# USB_CAMERA.net
KiCad netlist of a schematic drawn in Altium Designer
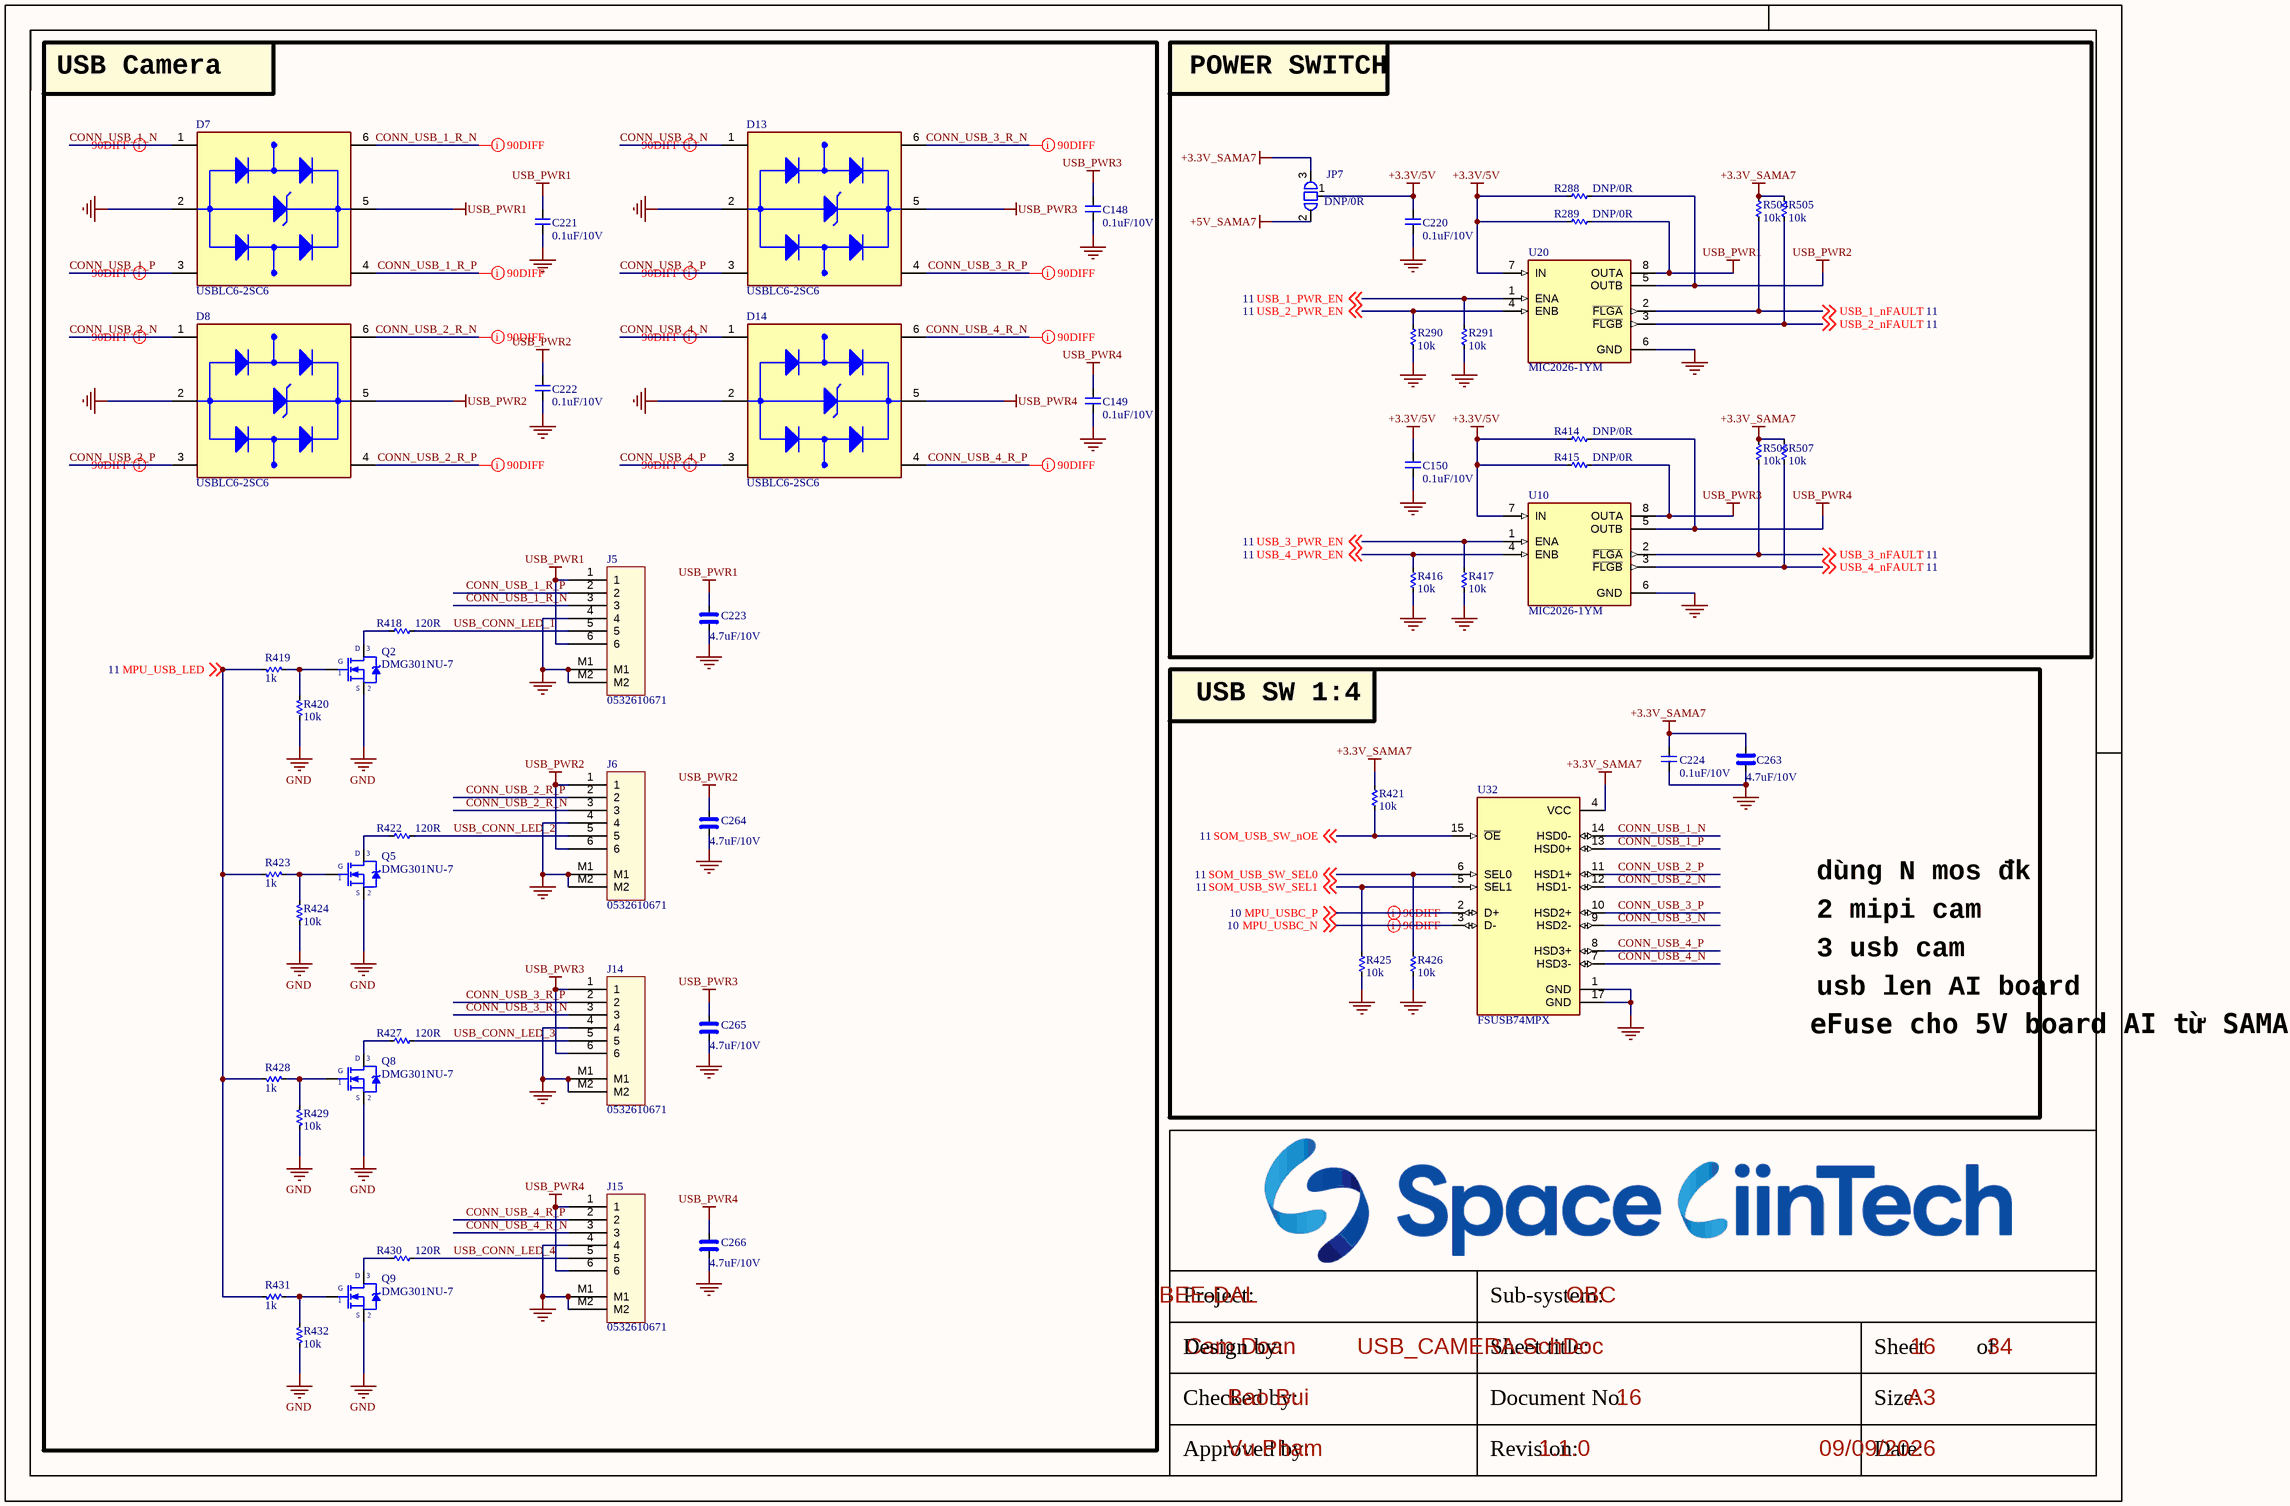
[diagram p0: USB_CAMERA.SchDoc]

(export (version "E")
  (design (tool "Eeschema 10.0.6"))
  (components
    (comp (ref "C148")
      (value "0.1uF/10V")
      (footprint "CAP_C_1005X50_L")
      (description "CAP")
      (libsource (lib "LABLIB") (part "_CAP_C_2"))
    )
    (comp (ref "C149")
      (value "0.1uF/10V")
      (footprint "CAP_C_1005X50_L")
      (description "CAP")
      (libsource (lib "LABLIB") (part "_CAP_C_2"))
    )
    (comp (ref "C150")
      (value "0.1uF/10V")
      (footprint "CAP_C_1005X50_L")
      (description "CAP")
      (libsource (lib "LABLIB") (part "_CAP_C_2"))
    )
    (comp (ref "C220")
      (value "0.1uF/10V")
      (footprint "CAP_C_1005X50_L")
      (description "CAP")
      (libsource (lib "LABLIB") (part "_CAP_C_2"))
    )
    (comp (ref "C221")
      (value "0.1uF/10V")
      (footprint "CAP_C_1005X50_L")
      (description "CAP")
      (libsource (lib "LABLIB") (part "_CAP_C_2"))
    )
    (comp (ref "C222")
      (value "0.1uF/10V")
      (footprint "CAP_C_1005X50_L")
      (description "CAP")
      (libsource (lib "LABLIB") (part "_CAP_C_2"))
    )
    (comp (ref "C223")
      (value "4.7uF/10V")
      (footprint "CAP_C_1005X60")
      (description "CAP CHIP High Value")
      (libsource (lib "LABLIB") (part "_CAP_C_High_2"))
    )
    (comp (ref "C224")
      (value "0.1uF/10V")
      (footprint "CAP_C_1005X50_L")
      (description "CAP CHIP")
      (libsource (lib "LABLIB") (part "_CAP_C_2"))
    )
    (comp (ref "C263")
      (value "4.7uF/10V")
      (footprint "CAP_C_1005X60")
      (description "CAP CHIP High Value")
      (libsource (lib "LABLIB") (part "_CAP_C_High_2"))
    )
    (comp (ref "C264")
      (value "4.7uF/10V")
      (footprint "CAP_C_1005X60")
      (description "CAP CHIP High Value")
      (libsource (lib "LABLIB") (part "_CAP_C_High_2"))
    )
    (comp (ref "C265")
      (value "4.7uF/10V")
      (footprint "CAP_C_1005X60")
      (description "CAP CHIP High Value")
      (libsource (lib "LABLIB") (part "_CAP_C_High_2"))
    )
    (comp (ref "C266")
      (value "4.7uF/10V")
      (footprint "CAP_C_1005X60")
      (description "CAP CHIP High Value")
      (libsource (lib "LABLIB") (part "_CAP_C_High_2"))
    )
    (comp (ref "D7")
      (value "USBLC6-2SC6")
      (footprint "SOT95P280X145-6N")
      (description "17V Clamp 5A (8/20Âµs) Ipp Tvs Diode Surface Mount SOT-23-6")
      (fields (field (name "MF") "STMicroelectronics"))
      (libsource (lib "USBLC6-2SC6") (part "USBLC6-2SC6"))
    )
    (comp (ref "D8")
      (value "USBLC6-2SC6")
      (footprint "SOT95P280X145-6N")
      (description "17V Clamp 5A (8/20Âµs) Ipp Tvs Diode Surface Mount SOT-23-6")
      (fields (field (name "MF") "STMicroelectronics"))
      (libsource (lib "USBLC6-2SC6") (part "USBLC6-2SC6"))
    )
    (comp (ref "D13")
      (value "USBLC6-2SC6")
      (footprint "SOT95P280X145-6N")
      (description "17V Clamp 5A (8/20Âµs) Ipp Tvs Diode Surface Mount SOT-23-6")
      (fields (field (name "MF") "STMicroelectronics"))
      (libsource (lib "USBLC6-2SC6") (part "USBLC6-2SC6"))
    )
    (comp (ref "D14")
      (value "USBLC6-2SC6")
      (footprint "SOT95P280X145-6N")
      (description "17V Clamp 5A (8/20Âµs) Ipp Tvs Diode Surface Mount SOT-23-6")
      (fields (field (name "MF") "STMicroelectronics"))
      (libsource (lib "USBLC6-2SC6") (part "USBLC6-2SC6"))
    )
    (comp (ref "J5")
      (value "0532610671")
      (footprint "MOLEX_0532610671")
      (libsource (lib "LABLIB") (part "Header 6x1_2M"))
    )
    (comp (ref "J6")
      (value "0532610671")
      (footprint "MOLEX_0532610671")
      (libsource (lib "LABLIB") (part "Header 6x1_2M"))
    )
    (comp (ref "J14")
      (value "0532610671")
      (footprint "MOLEX_0532610671")
      (libsource (lib "LABLIB") (part "Header 6x1_2M"))
    )
    (comp (ref "J15")
      (value "0532610671")
      (footprint "MOLEX_0532610671")
      (libsource (lib "LABLIB") (part "Header 6x1_2M"))
    )
    (comp (ref "JP7")
      (value "DNP/0R")
      (footprint "JUMPER_1-2_1608X60")
      (libsource (lib "LABLIB") (part "JUMPER_1_2"))
    )
    (comp (ref "Q2")
      (value "DMG301NU-7")
      (footprint "SOT95P240X120-3N")
      (libsource (lib "LABLIB") (part "MOSFET_N_GSD"))
    )
    (comp (ref "Q5")
      (value "DMG301NU-7")
      (footprint "SOT95P240X120-3N")
      (libsource (lib "LABLIB") (part "MOSFET_N_GSD"))
    )
    (comp (ref "Q8")
      (value "DMG301NU-7")
      (footprint "SOT95P240X120-3N")
      (libsource (lib "LABLIB") (part "MOSFET_N_GSD"))
    )
    (comp (ref "Q9")
      (value "DMG301NU-7")
      (footprint "SOT95P240X120-3N")
      (libsource (lib "LABLIB") (part "MOSFET_N_GSD"))
    )
    (comp (ref "R288")
      (value "DNP/0R")
      (footprint "RES_C_1005x30_L")
      (description "RES")
      (libsource (lib "LABLIB") (part "_RES_B_2"))
    )
    (comp (ref "R289")
      (value "DNP/0R")
      (footprint "RES_C_1005x30_L")
      (description "RES")
      (libsource (lib "LABLIB") (part "_RES_B_2"))
    )
    (comp (ref "R290")
      (value "10k")
      (footprint "RES_C_1005x30_L")
      (description "RES")
      (libsource (lib "LABLIB") (part "_RES_B_2"))
    )
    (comp (ref "R291")
      (value "10k")
      (footprint "RES_C_1005x30_L")
      (description "RES")
      (libsource (lib "LABLIB") (part "_RES_B_2"))
    )
    (comp (ref "R414")
      (value "DNP/0R")
      (footprint "RES_C_1005x30_L")
      (description "RES")
      (libsource (lib "LABLIB") (part "_RES_B_2"))
    )
    (comp (ref "R415")
      (value "DNP/0R")
      (footprint "RES_C_1005x30_L")
      (description "RES")
      (libsource (lib "LABLIB") (part "_RES_B_2"))
    )
    (comp (ref "R416")
      (value "10k")
      (footprint "RES_C_1005x30_L")
      (description "RES")
      (libsource (lib "LABLIB") (part "_RES_B_2"))
    )
    (comp (ref "R417")
      (value "10k")
      (footprint "RES_C_1005x30_L")
      (description "RES")
      (libsource (lib "LABLIB") (part "_RES_B_2"))
    )
    (comp (ref "R418")
      (value "120R")
      (footprint "RES_C_1005x30_L")
      (description "RES")
      (libsource (lib "LABLIB") (part "_RES_B_2"))
    )
    (comp (ref "R419")
      (value "1k")
      (footprint "RES_C_1005x30_L")
      (description "RES")
      (libsource (lib "LABLIB") (part "_RES_B_2"))
    )
    (comp (ref "R420")
      (value "10k")
      (footprint "RES_C_1005x30_L")
      (description "RES")
      (libsource (lib "LABLIB") (part "_RES_B_2"))
    )
    (comp (ref "R421")
      (value "10k")
      (footprint "RES_C_1005X40")
      (description "RES")
      (libsource (lib "LABLIB") (part "_RES_B_2"))
    )
    (comp (ref "R422")
      (value "120R")
      (footprint "RES_C_1005x30_L")
      (description "RES")
      (libsource (lib "LABLIB") (part "_RES_B_2"))
    )
    (comp (ref "R423")
      (value "1k")
      (footprint "RES_C_1005x30_L")
      (description "RES")
      (libsource (lib "LABLIB") (part "_RES_B_2"))
    )
    (comp (ref "R424")
      (value "10k")
      (footprint "RES_C_1005x30_L")
      (description "RES")
      (libsource (lib "LABLIB") (part "_RES_B_2"))
    )
    (comp (ref "R425")
      (value "10k")
      (footprint "RES_C_1005X40")
      (description "RES")
      (libsource (lib "LABLIB") (part "_RES_B_2"))
    )
    (comp (ref "R426")
      (value "10k")
      (footprint "RES_C_1005X40")
      (description "RES")
      (libsource (lib "LABLIB") (part "_RES_B_2"))
    )
    (comp (ref "R427")
      (value "120R")
      (footprint "RES_C_1005x30_L")
      (description "RES")
      (libsource (lib "LABLIB") (part "_RES_B_2"))
    )
    (comp (ref "R428")
      (value "1k")
      (footprint "RES_C_1005x30_L")
      (description "RES")
      (libsource (lib "LABLIB") (part "_RES_B_2"))
    )
    (comp (ref "R429")
      (value "10k")
      (footprint "RES_C_1005x30_L")
      (description "RES")
      (libsource (lib "LABLIB") (part "_RES_B_2"))
    )
    (comp (ref "R430")
      (value "120R")
      (footprint "RES_C_1005x30_L")
      (description "RES")
      (libsource (lib "LABLIB") (part "_RES_B_2"))
    )
    (comp (ref "R431")
      (value "1k")
      (footprint "RES_C_1005x30_L")
      (description "RES")
      (libsource (lib "LABLIB") (part "_RES_B_2"))
    )
    (comp (ref "R432")
      (value "10k")
      (footprint "RES_C_1005x30_L")
      (description "RES")
      (libsource (lib "LABLIB") (part "_RES_B_2"))
    )
    (comp (ref "R504")
      (value "10k")
      (footprint "RES_C_1005x30_L")
      (description "RES")
      (libsource (lib "LABLIB") (part "_RES_B_2"))
    )
    (comp (ref "R505")
      (value "10k")
      (footprint "RES_C_1005x30_L")
      (description "RES")
      (libsource (lib "LABLIB") (part "_RES_B_2"))
    )
    (comp (ref "R506")
      (value "10k")
      (footprint "RES_C_1005x30_L")
      (description "RES")
      (libsource (lib "LABLIB") (part "_RES_B_2"))
    )
    (comp (ref "R507")
      (value "10k")
      (footprint "RES_C_1005x30_L")
      (description "RES")
      (libsource (lib "LABLIB") (part "_RES_B_2"))
    )
    (comp (ref "U10")
      (value "MIC2026-1YM")
      (footprint "SOIC127P602X173-8N")
      (description "Power Switch/Driver 1:2 N-Channel 1.25A 8-SOIC")
      (fields (field (name "MF") "Microchip"))
      (libsource (lib "LABLIB") (part "IC_PWRSW_MIC2026-1YM"))
    )
    (comp (ref "U20")
      (value "MIC2026-1YM")
      (footprint "SOIC127P602X173-8N")
      (description "Power Switch/Driver 1:2 N-Channel 1.25A 8-SOIC")
      (fields (field (name "MF") "Microchip"))
      (libsource (lib "LABLIB") (part "IC_PWRSW_MIC2026-1YM"))
    )
    (comp (ref "U32")
      (value "FSUSB74MPX")
      (footprint "QFN50P300X300X80-17N")
      (description "USB Switch IC 1 Channel 16-MLP (3x3)")
      (fields (field (name "MF") "ON Semiconductor"))
      (libsource (lib "LABLIB") (part "IC_USB_SW_FSUSB74MPX"))
    )
  )
  (nets
    (net (code "1") (name "+3.3V_SAMA7") (class "Default")
      (node (ref "C224") (pin "2") (pinfunction "2_2") (pintype "passive"))
      (node (ref "C263") (pin "2") (pinfunction "2_2") (pintype "passive"))
      (node (ref "JP7") (pin "3") (pinfunction "3_3") (pintype "passive"))
      (node (ref "R421") (pin "1") (pinfunction "1_1") (pintype "passive"))
      (node (ref "R504") (pin "1") (pinfunction "1_1") (pintype "passive"))
      (node (ref "R505") (pin "1") (pinfunction "1_1") (pintype "passive"))
      (node (ref "R506") (pin "1") (pinfunction "1_1") (pintype "passive"))
      (node (ref "R507") (pin "1") (pinfunction "1_1") (pintype "passive"))
      (node (ref "U32") (pin "4") (pinfunction "VCC_4") (pintype "power_in"))
    )
    (net (code "2") (name "+3.3V{slash}5V") (class "Default")
      (node (ref "C150") (pin "2") (pinfunction "2_2") (pintype "passive"))
      (node (ref "C220") (pin "2") (pinfunction "2_2") (pintype "passive"))
      (node (ref "JP7") (pin "1") (pinfunction "1_1") (pintype "passive"))
      (node (ref "R288") (pin "2") (pinfunction "2_2") (pintype "passive"))
      (node (ref "R289") (pin "2") (pinfunction "2_2") (pintype "passive"))
      (node (ref "R414") (pin "2") (pinfunction "2_2") (pintype "passive"))
      (node (ref "R415") (pin "2") (pinfunction "2_2") (pintype "passive"))
      (node (ref "U10") (pin "7") (pinfunction "IN_7") (pintype "input"))
      (node (ref "U20") (pin "7") (pinfunction "IN_7") (pintype "input"))
    )
    (net (code "3") (name "+5V_SAMA7") (class "Default")
      (node (ref "JP7") (pin "2") (pinfunction "2_2") (pintype "passive"))
    )
    (net (code "4") (name "/CONN_USB_1_N") (class "Default")
      (node (ref "D7") (pin "1") (pinfunction "I/O1_IN_1") (pintype "passive"))
      (node (ref "U32") (pin "14") (pinfunction "HSD0-_14") (pintype "bidirectional"))
    )
    (net (code "5") (name "/CONN_USB_1_P") (class "Default")
      (node (ref "D7") (pin "3") (pinfunction "I/O2_IN_3") (pintype "passive"))
      (node (ref "U32") (pin "13") (pinfunction "HSD0+_13") (pintype "bidirectional"))
    )
    (net (code "6") (name "/CONN_USB_1_R_N") (class "Default")
      (node (ref "D7") (pin "6") (pinfunction "I/O1_OUT_6") (pintype "passive"))
      (node (ref "J5") (pin "3") (pinfunction "3_3") (pintype "passive"))
    )
    (net (code "7") (name "/CONN_USB_1_R_P") (class "Default")
      (node (ref "D7") (pin "4") (pinfunction "I/O2_OUT_4") (pintype "passive"))
      (node (ref "J5") (pin "2") (pinfunction "2_2") (pintype "passive"))
    )
    (net (code "8") (name "/CONN_USB_2_N") (class "Default")
      (node (ref "D8") (pin "1") (pinfunction "I/O1_IN_1") (pintype "passive"))
      (node (ref "U32") (pin "12") (pinfunction "HSD1-_12") (pintype "bidirectional"))
    )
    (net (code "9") (name "/CONN_USB_2_P") (class "Default")
      (node (ref "D8") (pin "3") (pinfunction "I/O2_IN_3") (pintype "passive"))
      (node (ref "U32") (pin "11") (pinfunction "HSD1+_11") (pintype "bidirectional"))
    )
    (net (code "10") (name "/CONN_USB_2_R_N") (class "Default")
      (node (ref "D8") (pin "6") (pinfunction "I/O1_OUT_6") (pintype "passive"))
      (node (ref "J6") (pin "3") (pinfunction "3_3") (pintype "passive"))
    )
    (net (code "11") (name "/CONN_USB_2_R_P") (class "Default")
      (node (ref "D8") (pin "4") (pinfunction "I/O2_OUT_4") (pintype "passive"))
      (node (ref "J6") (pin "2") (pinfunction "2_2") (pintype "passive"))
    )
    (net (code "12") (name "/CONN_USB_3_N") (class "Default")
      (node (ref "D13") (pin "1") (pinfunction "I/O1_IN_1") (pintype "passive"))
      (node (ref "U32") (pin "9") (pinfunction "HSD2-_9") (pintype "bidirectional"))
    )
    (net (code "13") (name "/CONN_USB_3_P") (class "Default")
      (node (ref "D13") (pin "3") (pinfunction "I/O2_IN_3") (pintype "passive"))
      (node (ref "U32") (pin "10") (pinfunction "HSD2+_10") (pintype "bidirectional"))
    )
    (net (code "14") (name "/CONN_USB_3_R_N") (class "Default")
      (node (ref "D13") (pin "6") (pinfunction "I/O1_OUT_6") (pintype "passive"))
      (node (ref "J14") (pin "3") (pinfunction "3_3") (pintype "passive"))
    )
    (net (code "15") (name "/CONN_USB_3_R_P") (class "Default")
      (node (ref "D13") (pin "4") (pinfunction "I/O2_OUT_4") (pintype "passive"))
      (node (ref "J14") (pin "2") (pinfunction "2_2") (pintype "passive"))
    )
    (net (code "16") (name "/CONN_USB_4_N") (class "Default")
      (node (ref "D14") (pin "1") (pinfunction "I/O1_IN_1") (pintype "passive"))
      (node (ref "U32") (pin "7") (pinfunction "HSD3-_7") (pintype "bidirectional"))
    )
    (net (code "17") (name "/CONN_USB_4_P") (class "Default")
      (node (ref "D14") (pin "3") (pinfunction "I/O2_IN_3") (pintype "passive"))
      (node (ref "U32") (pin "8") (pinfunction "HSD3+_8") (pintype "bidirectional"))
    )
    (net (code "18") (name "/CONN_USB_4_R_N") (class "Default")
      (node (ref "D14") (pin "6") (pinfunction "I/O1_OUT_6") (pintype "passive"))
      (node (ref "J15") (pin "3") (pinfunction "3_3") (pintype "passive"))
    )
    (net (code "19") (name "/CONN_USB_4_R_P") (class "Default")
      (node (ref "D14") (pin "4") (pinfunction "I/O2_OUT_4") (pintype "passive"))
      (node (ref "J15") (pin "2") (pinfunction "2_2") (pintype "passive"))
    )
    (net (code "20") (name "/USB_CONN_LED_1") (class "Default")
      (node (ref "J5") (pin "5") (pinfunction "5_5") (pintype "passive"))
      (node (ref "R418") (pin "2") (pinfunction "2_2") (pintype "passive"))
    )
    (net (code "21") (name "/USB_CONN_LED_2") (class "Default")
      (node (ref "J6") (pin "5") (pinfunction "5_5") (pintype "passive"))
      (node (ref "R422") (pin "2") (pinfunction "2_2") (pintype "passive"))
    )
    (net (code "22") (name "/USB_CONN_LED_3") (class "Default")
      (node (ref "J14") (pin "5") (pinfunction "5_5") (pintype "passive"))
      (node (ref "R427") (pin "2") (pinfunction "2_2") (pintype "passive"))
    )
    (net (code "23") (name "/USB_CONN_LED_4") (class "Default")
      (node (ref "J15") (pin "5") (pinfunction "5_5") (pintype "passive"))
      (node (ref "R430") (pin "2") (pinfunction "2_2") (pintype "passive"))
    )
    (net (code "24") (name "GND") (class "Default")
      (node (ref "C148") (pin "1") (pinfunction "1_1") (pintype "passive"))
      (node (ref "C149") (pin "1") (pinfunction "1_1") (pintype "passive"))
      (node (ref "C150") (pin "1") (pinfunction "1_1") (pintype "passive"))
      (node (ref "C220") (pin "1") (pinfunction "1_1") (pintype "passive"))
      (node (ref "C221") (pin "1") (pinfunction "1_1") (pintype "passive"))
      (node (ref "C222") (pin "1") (pinfunction "1_1") (pintype "passive"))
      (node (ref "C223") (pin "2") (pinfunction "2_2") (pintype "passive"))
      (node (ref "C224") (pin "1") (pinfunction "1_1") (pintype "passive"))
      (node (ref "C263") (pin "1") (pinfunction "1_1") (pintype "passive"))
      (node (ref "C264") (pin "2") (pinfunction "2_2") (pintype "passive"))
      (node (ref "C265") (pin "2") (pinfunction "2_2") (pintype "passive"))
      (node (ref "C266") (pin "2") (pinfunction "2_2") (pintype "passive"))
      (node (ref "D13") (pin "2") (pinfunction "GND_2") (pintype "power_in"))
      (node (ref "D14") (pin "2") (pinfunction "GND_2") (pintype "power_in"))
      (node (ref "D7") (pin "2") (pinfunction "GND_2") (pintype "power_in"))
      (node (ref "D8") (pin "2") (pinfunction "GND_2") (pintype "power_in"))
      (node (ref "J14") (pin "4") (pinfunction "4_4") (pintype "passive"))
      (node (ref "J14") (pin "M1") (pinfunction "M1_M1") (pintype "passive"))
      (node (ref "J14") (pin "M2") (pinfunction "M2_M2") (pintype "passive"))
      (node (ref "J15") (pin "4") (pinfunction "4_4") (pintype "passive"))
      (node (ref "J15") (pin "M1") (pinfunction "M1_M1") (pintype "passive"))
      (node (ref "J15") (pin "M2") (pinfunction "M2_M2") (pintype "passive"))
      (node (ref "J5") (pin "4") (pinfunction "4_4") (pintype "passive"))
      (node (ref "J5") (pin "M1") (pinfunction "M1_M1") (pintype "passive"))
      (node (ref "J5") (pin "M2") (pinfunction "M2_M2") (pintype "passive"))
      (node (ref "J6") (pin "4") (pinfunction "4_4") (pintype "passive"))
      (node (ref "J6") (pin "M1") (pinfunction "M1_M1") (pintype "passive"))
      (node (ref "J6") (pin "M2") (pinfunction "M2_M2") (pintype "passive"))
      (node (ref "Q2") (pin "2") (pinfunction "S_2") (pintype "passive"))
      (node (ref "Q5") (pin "2") (pinfunction "S_2") (pintype "passive"))
      (node (ref "Q8") (pin "2") (pinfunction "S_2") (pintype "passive"))
      (node (ref "Q9") (pin "2") (pinfunction "S_2") (pintype "passive"))
      (node (ref "R290") (pin "2") (pinfunction "2_2") (pintype "passive"))
      (node (ref "R291") (pin "2") (pinfunction "2_2") (pintype "passive"))
      (node (ref "R416") (pin "2") (pinfunction "2_2") (pintype "passive"))
      (node (ref "R417") (pin "2") (pinfunction "2_2") (pintype "passive"))
      (node (ref "R420") (pin "1") (pinfunction "1_1") (pintype "passive"))
      (node (ref "R424") (pin "1") (pinfunction "1_1") (pintype "passive"))
      (node (ref "R425") (pin "2") (pinfunction "2_2") (pintype "passive"))
      (node (ref "R426") (pin "2") (pinfunction "2_2") (pintype "passive"))
      (node (ref "R429") (pin "1") (pinfunction "1_1") (pintype "passive"))
      (node (ref "R432") (pin "1") (pinfunction "1_1") (pintype "passive"))
      (node (ref "U10") (pin "6") (pinfunction "GND_6") (pintype "power_in"))
      (node (ref "U20") (pin "6") (pinfunction "GND_6") (pintype "power_in"))
      (node (ref "U32") (pin "1") (pinfunction "GND_1") (pintype "power_in"))
      (node (ref "U32") (pin "17") (pinfunction "GND_17") (pintype "power_in"))
    )
    (net (code "25") (name "MPU_USBC_N") (class "Default")
      (node (ref "U32") (pin "3") (pinfunction "D-_3") (pintype "bidirectional"))
    )
    (net (code "26") (name "MPU_USBC_P") (class "Default")
      (node (ref "U32") (pin "2") (pinfunction "D+_2") (pintype "bidirectional"))
    )
    (net (code "27") (name "MPU_USB_LED") (class "Default")
      (node (ref "R419") (pin "1") (pinfunction "1_1") (pintype "passive"))
      (node (ref "R423") (pin "1") (pinfunction "1_1") (pintype "passive"))
      (node (ref "R428") (pin "1") (pinfunction "1_1") (pintype "passive"))
      (node (ref "R431") (pin "1") (pinfunction "1_1") (pintype "passive"))
    )
    (net (code "28") (name "Net-(Q2-D)") (class "Default")
      (node (ref "Q2") (pin "3") (pinfunction "D_3") (pintype "passive"))
      (node (ref "R418") (pin "1") (pinfunction "1_1") (pintype "passive"))
    )
    (net (code "29") (name "Net-(Q2-G)") (class "Default")
      (node (ref "Q2") (pin "1") (pinfunction "G_1") (pintype "passive"))
      (node (ref "R419") (pin "2") (pinfunction "2_2") (pintype "passive"))
      (node (ref "R420") (pin "2") (pinfunction "2_2") (pintype "passive"))
    )
    (net (code "30") (name "Net-(Q5-D)") (class "Default")
      (node (ref "Q5") (pin "3") (pinfunction "D_3") (pintype "passive"))
      (node (ref "R422") (pin "1") (pinfunction "1_1") (pintype "passive"))
    )
    (net (code "31") (name "Net-(Q5-G)") (class "Default")
      (node (ref "Q5") (pin "1") (pinfunction "G_1") (pintype "passive"))
      (node (ref "R423") (pin "2") (pinfunction "2_2") (pintype "passive"))
      (node (ref "R424") (pin "2") (pinfunction "2_2") (pintype "passive"))
    )
    (net (code "32") (name "Net-(Q8-D)") (class "Default")
      (node (ref "Q8") (pin "3") (pinfunction "D_3") (pintype "passive"))
      (node (ref "R427") (pin "1") (pinfunction "1_1") (pintype "passive"))
    )
    (net (code "33") (name "Net-(Q8-G)") (class "Default")
      (node (ref "Q8") (pin "1") (pinfunction "G_1") (pintype "passive"))
      (node (ref "R428") (pin "2") (pinfunction "2_2") (pintype "passive"))
      (node (ref "R429") (pin "2") (pinfunction "2_2") (pintype "passive"))
    )
    (net (code "34") (name "Net-(Q9-D)") (class "Default")
      (node (ref "Q9") (pin "3") (pinfunction "D_3") (pintype "passive"))
      (node (ref "R430") (pin "1") (pinfunction "1_1") (pintype "passive"))
    )
    (net (code "35") (name "Net-(Q9-G)") (class "Default")
      (node (ref "Q9") (pin "1") (pinfunction "G_1") (pintype "passive"))
      (node (ref "R431") (pin "2") (pinfunction "2_2") (pintype "passive"))
      (node (ref "R432") (pin "2") (pinfunction "2_2") (pintype "passive"))
    )
    (net (code "36") (name "SOM_USB_SW_SEL0") (class "Default")
      (node (ref "R426") (pin "1") (pinfunction "1_1") (pintype "passive"))
      (node (ref "U32") (pin "6") (pinfunction "SEL0_6") (pintype "input"))
    )
    (net (code "37") (name "SOM_USB_SW_SEL1") (class "Default")
      (node (ref "R425") (pin "1") (pinfunction "1_1") (pintype "passive"))
      (node (ref "U32") (pin "5") (pinfunction "SEL1_5") (pintype "input"))
    )
    (net (code "38") (name "SOM_USB_SW_nOE") (class "Default")
      (node (ref "R421") (pin "2") (pinfunction "2_2") (pintype "passive"))
      (node (ref "U32") (pin "15") (pinfunction "~{OE}_15") (pintype "input"))
    )
    (net (code "39") (name "USB_1_PWR_EN") (class "Default")
      (node (ref "R291") (pin "1") (pinfunction "1_1") (pintype "passive"))
      (node (ref "U20") (pin "1") (pinfunction "ENA_1") (pintype "input"))
    )
    (net (code "40") (name "USB_1_nFAULT") (class "Default")
      (node (ref "R504") (pin "2") (pinfunction "2_2") (pintype "passive"))
      (node (ref "U20") (pin "2") (pinfunction "~{FLGA}_2") (pintype "output"))
    )
    (net (code "41") (name "USB_2_PWR_EN") (class "Default")
      (node (ref "R290") (pin "1") (pinfunction "1_1") (pintype "passive"))
      (node (ref "U20") (pin "4") (pinfunction "ENB_4") (pintype "input"))
    )
    (net (code "42") (name "USB_2_nFAULT") (class "Default")
      (node (ref "R505") (pin "2") (pinfunction "2_2") (pintype "passive"))
      (node (ref "U20") (pin "3") (pinfunction "~{FLGB}_3") (pintype "output"))
    )
    (net (code "43") (name "USB_3_PWR_EN") (class "Default")
      (node (ref "R417") (pin "1") (pinfunction "1_1") (pintype "passive"))
      (node (ref "U10") (pin "1") (pinfunction "ENA_1") (pintype "input"))
    )
    (net (code "44") (name "USB_3_nFAULT") (class "Default")
      (node (ref "R506") (pin "2") (pinfunction "2_2") (pintype "passive"))
      (node (ref "U10") (pin "2") (pinfunction "~{FLGA}_2") (pintype "output"))
    )
    (net (code "45") (name "USB_4_PWR_EN") (class "Default")
      (node (ref "R416") (pin "1") (pinfunction "1_1") (pintype "passive"))
      (node (ref "U10") (pin "4") (pinfunction "ENB_4") (pintype "input"))
    )
    (net (code "46") (name "USB_4_nFAULT") (class "Default")
      (node (ref "R507") (pin "2") (pinfunction "2_2") (pintype "passive"))
      (node (ref "U10") (pin "3") (pinfunction "~{FLGB}_3") (pintype "output"))
    )
    (net (code "47") (name "USB_PWR1") (class "Default")
      (node (ref "C221") (pin "2") (pinfunction "2_2") (pintype "passive"))
      (node (ref "C223") (pin "1") (pinfunction "1_1") (pintype "passive"))
      (node (ref "D7") (pin "5") (pinfunction "VBUS_5") (pintype "power_in"))
      (node (ref "J5") (pin "1") (pinfunction "1_1") (pintype "passive"))
      (node (ref "J5") (pin "6") (pinfunction "6_6") (pintype "passive"))
      (node (ref "R289") (pin "1") (pinfunction "1_1") (pintype "passive"))
      (node (ref "U20") (pin "8") (pinfunction "OUTA_8") (pintype "passive"))
    )
    (net (code "48") (name "USB_PWR2") (class "Default")
      (node (ref "C222") (pin "2") (pinfunction "2_2") (pintype "passive"))
      (node (ref "C264") (pin "1") (pinfunction "1_1") (pintype "passive"))
      (node (ref "D8") (pin "5") (pinfunction "VBUS_5") (pintype "power_in"))
      (node (ref "J6") (pin "1") (pinfunction "1_1") (pintype "passive"))
      (node (ref "J6") (pin "6") (pinfunction "6_6") (pintype "passive"))
      (node (ref "R288") (pin "1") (pinfunction "1_1") (pintype "passive"))
      (node (ref "U20") (pin "5") (pinfunction "OUTB_5") (pintype "passive"))
    )
    (net (code "49") (name "USB_PWR3") (class "Default")
      (node (ref "C148") (pin "2") (pinfunction "2_2") (pintype "passive"))
      (node (ref "C265") (pin "1") (pinfunction "1_1") (pintype "passive"))
      (node (ref "D13") (pin "5") (pinfunction "VBUS_5") (pintype "power_in"))
      (node (ref "J14") (pin "1") (pinfunction "1_1") (pintype "passive"))
      (node (ref "J14") (pin "6") (pinfunction "6_6") (pintype "passive"))
      (node (ref "R415") (pin "1") (pinfunction "1_1") (pintype "passive"))
      (node (ref "U10") (pin "8") (pinfunction "OUTA_8") (pintype "passive"))
    )
    (net (code "50") (name "USB_PWR4") (class "Default")
      (node (ref "C149") (pin "2") (pinfunction "2_2") (pintype "passive"))
      (node (ref "C266") (pin "1") (pinfunction "1_1") (pintype "passive"))
      (node (ref "D14") (pin "5") (pinfunction "VBUS_5") (pintype "power_in"))
      (node (ref "J15") (pin "1") (pinfunction "1_1") (pintype "passive"))
      (node (ref "J15") (pin "6") (pinfunction "6_6") (pintype "passive"))
      (node (ref "R414") (pin "1") (pinfunction "1_1") (pintype "passive"))
      (node (ref "U10") (pin "5") (pinfunction "OUTB_5") (pintype "passive"))
    )
  )
)
